# ESP01_Breakout.net
KiCad netlist of a schematic drawn in EAGLE
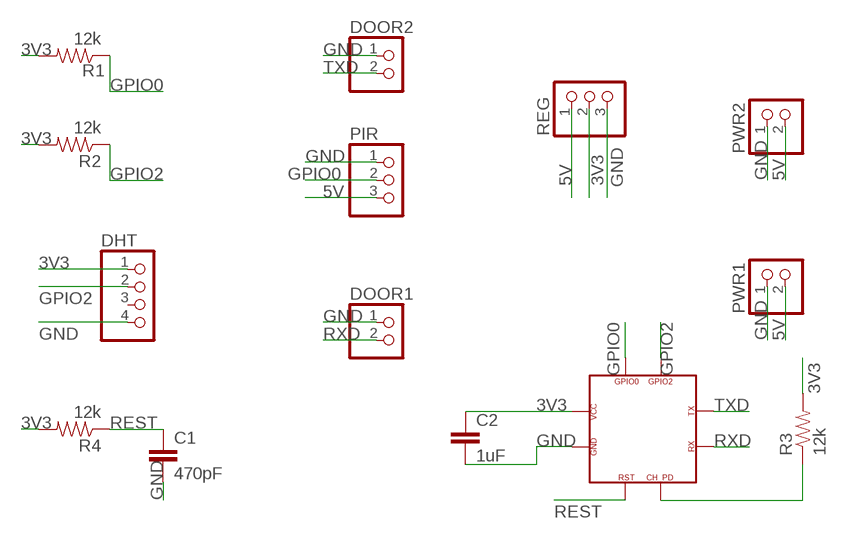
[diagram p0: schematic, sheet 1]

(export (version "E")
  (design (tool "Eeschema 10.0.6"))
  (components
    (comp (ref "C1")
      (value "470pF")
      (footprint "eagle-import:CAP-PTH-SMALLEZ")
      (libsource (lib "eagle-import") (part "CAPEZ"))
    )
    (comp (ref "C2")
      (value "1uF")
      (footprint "eagle-import:CAP-PTH-SMALLEZ")
      (libsource (lib "eagle-import") (part "CAPEZ"))
    )
    (comp (ref "DHT")
      (value "PINHD-1X4")
      (footprint "eagle-import:1X04")
      (libsource (lib "eagle-import") (part "PINHD-1X4"))
    )
    (comp (ref "DOOR1")
      (value "PINHD-1X2/90")
      (footprint "eagle-import:1X02_90")
      (libsource (lib "eagle-import") (part "PINHD-1X2/90"))
    )
    (comp (ref "DOOR2")
      (value "PINHD-1X2/90")
      (footprint "eagle-import:1X02_90")
      (libsource (lib "eagle-import") (part "PINHD-1X2/90"))
    )
    (comp (ref "PIR")
      (value "PINHD-1X3")
      (footprint "eagle-import:1X03")
      (libsource (lib "eagle-import") (part "PINHD-1X3"))
    )
    (comp (ref "PWR1")
      (value "PINHD-1X2/90")
      (footprint "eagle-import:1X02_90")
      (libsource (lib "eagle-import") (part "PINHD-1X2/90"))
    )
    (comp (ref "PWR2")
      (value "PINHD-1X2/90")
      (footprint "eagle-import:1X02_90")
      (libsource (lib "eagle-import") (part "PINHD-1X2/90"))
    )
    (comp (ref "R1")
      (value "12k")
      (footprint "eagle-import:AXIAL-0.4")
      (libsource (lib "eagle-import") (part "RESISTORPTH-1/4W"))
    )
    (comp (ref "R2")
      (value "12k")
      (footprint "eagle-import:AXIAL-0.4")
      (libsource (lib "eagle-import") (part "RESISTORPTH-1/4W"))
    )
    (comp (ref "R3")
      (value "12k")
      (footprint "eagle-import:AXIAL-0.4")
      (libsource (lib "eagle-import") (part "RESISTORPTH-1/4W"))
    )
    (comp (ref "R4")
      (value "12k")
      (footprint "eagle-import:AXIAL-0.4")
      (libsource (lib "eagle-import") (part "RESISTORPTH-1/4W"))
    )
    (comp (ref "REG")
      (value "PINHD-1X3")
      (footprint "eagle-import:1X03")
      (libsource (lib "eagle-import") (part "PINHD-1X3"))
    )
    (comp (ref "U$2")
      (value "ESP-01")
      (footprint "eagle-import:ESP-01")
      (libsource (lib "eagle-import") (part "ESP-01"))
    )
  )
  (nets
    (net (code "1") (name "/3V3") (class "Default")
      (node (ref "C2") (pin "1") (pinfunction "1_1") (pintype "passive"))
      (node (ref "DHT") (pin "1") (pinfunction "1_1") (pintype "passive"))
      (node (ref "R1") (pin "P$2") (pinfunction "2_P$2") (pintype "passive"))
      (node (ref "R2") (pin "P$2") (pinfunction "2_P$2") (pintype "passive"))
      (node (ref "R3") (pin "P$2") (pinfunction "2_P$2") (pintype "passive"))
      (node (ref "R4") (pin "P$2") (pinfunction "2_P$2") (pintype "passive"))
      (node (ref "REG") (pin "2") (pinfunction "2_2") (pintype "passive"))
      (node (ref "U$2") (pin "VCC") (pinfunction "VCC_VCC") (pintype "bidirectional"))
    )
    (net (code "2") (name "/5V") (class "Default")
      (node (ref "PIR") (pin "3") (pinfunction "3_3") (pintype "passive"))
      (node (ref "PWR1") (pin "2") (pinfunction "2_2") (pintype "passive"))
      (node (ref "PWR2") (pin "2") (pinfunction "2_2") (pintype "passive"))
      (node (ref "REG") (pin "1") (pinfunction "1_1") (pintype "passive"))
    )
    (net (code "3") (name "/GND") (class "Default")
      (node (ref "C1") (pin "2") (pinfunction "2_2") (pintype "passive"))
      (node (ref "C2") (pin "2") (pinfunction "2_2") (pintype "passive"))
      (node (ref "DHT") (pin "4") (pinfunction "4_4") (pintype "passive"))
      (node (ref "DOOR1") (pin "1") (pinfunction "1_1") (pintype "passive"))
      (node (ref "DOOR2") (pin "1") (pinfunction "1_1") (pintype "passive"))
      (node (ref "PIR") (pin "1") (pinfunction "1_1") (pintype "passive"))
      (node (ref "PWR1") (pin "1") (pinfunction "1_1") (pintype "passive"))
      (node (ref "PWR2") (pin "1") (pinfunction "1_1") (pintype "passive"))
      (node (ref "REG") (pin "3") (pinfunction "3_3") (pintype "passive"))
      (node (ref "U$2") (pin "GND") (pinfunction "GND_GND") (pintype "bidirectional"))
    )
    (net (code "4") (name "/GPIO0") (class "Default")
      (node (ref "PIR") (pin "2") (pinfunction "2_2") (pintype "passive"))
      (node (ref "R1") (pin "P$1") (pinfunction "1_P$1") (pintype "passive"))
      (node (ref "U$2") (pin "GPIO0") (pinfunction "GPIO0_GPIO0") (pintype "bidirectional"))
    )
    (net (code "5") (name "/GPIO2") (class "Default")
      (node (ref "DHT") (pin "2") (pinfunction "2_2") (pintype "passive"))
      (node (ref "R2") (pin "P$1") (pinfunction "1_P$1") (pintype "passive"))
      (node (ref "U$2") (pin "GPIO2") (pinfunction "GPIO2_GPIO2") (pintype "bidirectional"))
    )
    (net (code "6") (name "/REST") (class "Default")
      (node (ref "C1") (pin "1") (pinfunction "1_1") (pintype "passive"))
      (node (ref "R4") (pin "P$1") (pinfunction "1_P$1") (pintype "passive"))
      (node (ref "U$2") (pin "RST") (pinfunction "RST_RST") (pintype "bidirectional"))
    )
    (net (code "7") (name "/RXD") (class "Default")
      (node (ref "DOOR1") (pin "2") (pinfunction "2_2") (pintype "passive"))
      (node (ref "U$2") (pin "RXD") (pinfunction "RX_RXD") (pintype "bidirectional"))
    )
    (net (code "8") (name "/TXD") (class "Default")
      (node (ref "DOOR2") (pin "2") (pinfunction "2_2") (pintype "passive"))
      (node (ref "U$2") (pin "TXD") (pinfunction "TX_TXD") (pintype "bidirectional"))
    )
    (net (code "9") (name "Net-(R3-1)") (class "Default")
      (node (ref "R3") (pin "P$1") (pinfunction "1_P$1") (pintype "passive"))
      (node (ref "U$2") (pin "CH_PD") (pinfunction "CP_PD_CH_PD") (pintype "bidirectional"))
    )
    (net (code "10") (name "unconnected-(DHT-Pad3)") (class "Default")
      (node (ref "DHT") (pin "3") (pinfunction "3_3") (pintype "passive"))
    )
  )
)
